# Wave_Fold_Osc_CTRL_V2.net
KiCad netlist of a schematic drawn in EAGLE
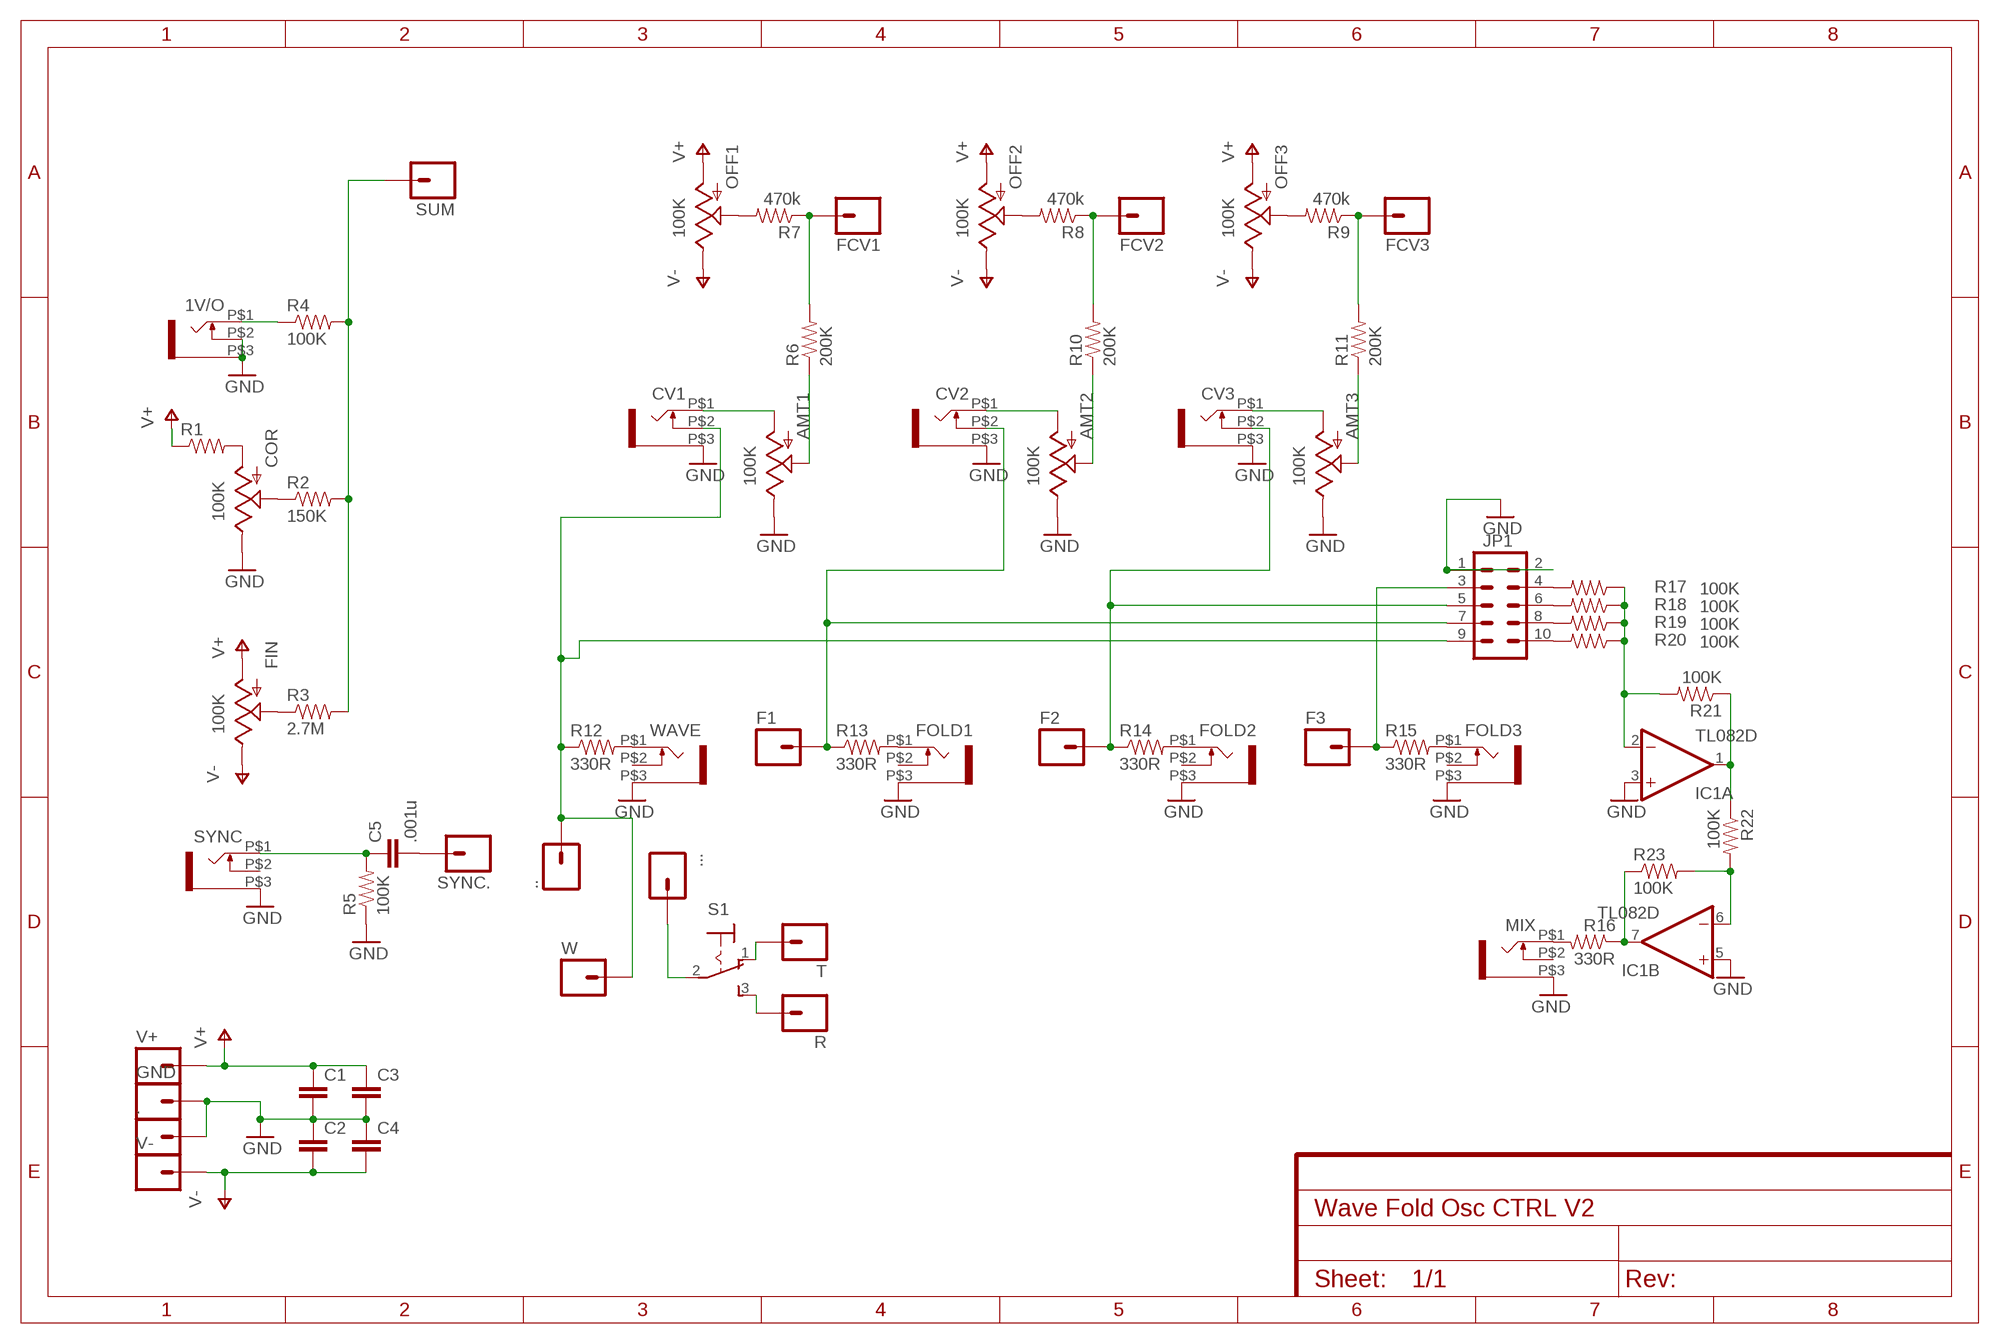
[diagram p0: schematic, sheet 1]

(export (version "E")
  (design (tool "Eeschema 10.0.6"))
  (components
    (comp (ref ".")
      (value "M01PTH")
      (footprint "eagle-import:1X01")
      (libsource (lib "eagle-import") (part "M01PTH"))
    )
    (comp (ref "..")
      (value "M01PTH")
      (footprint "eagle-import:1X01")
      (libsource (lib "eagle-import") (part "M01PTH"))
    )
    (comp (ref "...")
      (value "M01PTH")
      (footprint "eagle-import:1X01")
      (libsource (lib "eagle-import") (part "M01PTH"))
    )
    (comp (ref "1V/O")
      (value "WQP-PJ301M-12_JACK")
      (footprint "eagle-import:WQP-PJ301M-12_JACK")
      (libsource (lib "eagle-import") (part "WQP-PJ301M-12_JACK"))
    )
    (comp (ref "AMT1")
      (value "100K")
      (footprint "eagle-import:ALPS_POT")
      (libsource (lib "eagle-import") (part "POT"))
    )
    (comp (ref "AMT2")
      (value "100K")
      (footprint "eagle-import:ALPS_POT")
      (libsource (lib "eagle-import") (part "POT"))
    )
    (comp (ref "AMT3")
      (value "100K")
      (footprint "eagle-import:ALPS_POT")
      (libsource (lib "eagle-import") (part "POT"))
    )
    (comp (ref "C1")
      (value "CAP0805")
      (footprint "eagle-import:0805")
      (libsource (lib "eagle-import") (part "CAP0805"))
    )
    (comp (ref "C2")
      (value "CAP0805")
      (footprint "eagle-import:0805")
      (libsource (lib "eagle-import") (part "CAP0805"))
    )
    (comp (ref "C3")
      (value "CAP0805")
      (footprint "eagle-import:0805")
      (libsource (lib "eagle-import") (part "CAP0805"))
    )
    (comp (ref "C4")
      (value "CAP0805")
      (footprint "eagle-import:0805")
      (libsource (lib "eagle-import") (part "CAP0805"))
    )
    (comp (ref "C5")
      (value ".001u")
      (footprint "eagle-import:0805")
      (libsource (lib "eagle-import") (part "CAP0805"))
    )
    (comp (ref "COR")
      (value "100K")
      (footprint "eagle-import:ALPS_POT")
      (libsource (lib "eagle-import") (part "POT"))
    )
    (comp (ref "CV1")
      (value "WQP-PJ301M-12_JACK")
      (footprint "eagle-import:WQP-PJ301M-12_JACK")
      (libsource (lib "eagle-import") (part "WQP-PJ301M-12_JACK"))
    )
    (comp (ref "CV2")
      (value "WQP-PJ301M-12_JACK")
      (footprint "eagle-import:WQP-PJ301M-12_JACK")
      (libsource (lib "eagle-import") (part "WQP-PJ301M-12_JACK"))
    )
    (comp (ref "CV3")
      (value "WQP-PJ301M-12_JACK")
      (footprint "eagle-import:WQP-PJ301M-12_JACK")
      (libsource (lib "eagle-import") (part "WQP-PJ301M-12_JACK"))
    )
    (comp (ref "F1")
      (value "M01PTH")
      (footprint "eagle-import:1X01")
      (libsource (lib "eagle-import") (part "M01PTH"))
    )
    (comp (ref "F2")
      (value "M01PTH")
      (footprint "eagle-import:1X01")
      (libsource (lib "eagle-import") (part "M01PTH"))
    )
    (comp (ref "F3")
      (value "M01PTH")
      (footprint "eagle-import:1X01")
      (libsource (lib "eagle-import") (part "M01PTH"))
    )
    (comp (ref "FCV1")
      (value "M01PTH")
      (footprint "eagle-import:1X01")
      (libsource (lib "eagle-import") (part "M01PTH"))
    )
    (comp (ref "FCV2")
      (value "M01PTH")
      (footprint "eagle-import:1X01")
      (libsource (lib "eagle-import") (part "M01PTH"))
    )
    (comp (ref "FCV3")
      (value "M01PTH")
      (footprint "eagle-import:1X01")
      (libsource (lib "eagle-import") (part "M01PTH"))
    )
    (comp (ref "FIN")
      (value "100K")
      (footprint "eagle-import:ALPS_POT")
      (libsource (lib "eagle-import") (part "POT"))
    )
    (comp (ref "FOLD1")
      (value "WQP-PJ301M-12_JACK")
      (footprint "eagle-import:WQP-PJ301M-12_JACK")
      (libsource (lib "eagle-import") (part "WQP-PJ301M-12_JACK"))
    )
    (comp (ref "FOLD2")
      (value "WQP-PJ301M-12_JACK")
      (footprint "eagle-import:WQP-PJ301M-12_JACK")
      (libsource (lib "eagle-import") (part "WQP-PJ301M-12_JACK"))
    )
    (comp (ref "FOLD3")
      (value "WQP-PJ301M-12_JACK")
      (footprint "eagle-import:WQP-PJ301M-12_JACK")
      (libsource (lib "eagle-import") (part "WQP-PJ301M-12_JACK"))
    )
    (comp (ref "GND")
      (value "M01PTH")
      (footprint "eagle-import:1X01")
      (libsource (lib "eagle-import") (part "M01PTH"))
    )
    (comp (ref "IC1")
      (value "TL082D")
      (footprint "eagle-import:SO08")
      (libsource (lib "eagle-import") (part "TL082D"))
    )
    (comp (ref "JP1")
      (value "M05X2NO_SILK")
      (footprint "eagle-import:2X5_NOSILK")
      (libsource (lib "eagle-import") (part "M05X2NO_SILK"))
    )
    (comp (ref "MIX")
      (value "WQP-PJ301M-12_JACK")
      (footprint "eagle-import:WQP-PJ301M-12_JACK")
      (libsource (lib "eagle-import") (part "WQP-PJ301M-12_JACK"))
    )
    (comp (ref "OFF1")
      (value "100K")
      (footprint "eagle-import:ALPS_POT")
      (libsource (lib "eagle-import") (part "POT"))
    )
    (comp (ref "OFF2")
      (value "100K")
      (footprint "eagle-import:ALPS_POT")
      (libsource (lib "eagle-import") (part "POT"))
    )
    (comp (ref "OFF3")
      (value "100K")
      (footprint "eagle-import:ALPS_POT")
      (libsource (lib "eagle-import") (part "POT"))
    )
    (comp (ref "R")
      (value "M01PTH")
      (footprint "eagle-import:1X01")
      (libsource (lib "eagle-import") (part "M01PTH"))
    )
    (comp (ref "R1")
      (value "RESISTOR0805-RES")
      (footprint "eagle-import:0805")
      (libsource (lib "eagle-import") (part "RESISTOR0805-RES"))
    )
    (comp (ref "R2")
      (value "150K")
      (footprint "eagle-import:0805")
      (libsource (lib "eagle-import") (part "RESISTOR0805-RES"))
    )
    (comp (ref "R3")
      (value "2.7M")
      (footprint "eagle-import:0805")
      (libsource (lib "eagle-import") (part "RESISTOR0805-RES"))
    )
    (comp (ref "R4")
      (value "100K")
      (footprint "eagle-import:0805")
      (libsource (lib "eagle-import") (part "RESISTOR0805-RES"))
    )
    (comp (ref "R5")
      (value "100K")
      (footprint "eagle-import:0805")
      (libsource (lib "eagle-import") (part "RESISTOR0805-RES"))
    )
    (comp (ref "R6")
      (value "200K")
      (footprint "eagle-import:0805")
      (libsource (lib "eagle-import") (part "RESISTOR0805-RES"))
    )
    (comp (ref "R7")
      (value "470k")
      (footprint "eagle-import:0805")
      (libsource (lib "eagle-import") (part "RESISTOR0805-RES"))
    )
    (comp (ref "R8")
      (value "470k")
      (footprint "eagle-import:0805")
      (libsource (lib "eagle-import") (part "RESISTOR0805-RES"))
    )
    (comp (ref "R9")
      (value "470k")
      (footprint "eagle-import:0805")
      (libsource (lib "eagle-import") (part "RESISTOR0805-RES"))
    )
    (comp (ref "R10")
      (value "200K")
      (footprint "eagle-import:0805")
      (libsource (lib "eagle-import") (part "RESISTOR0805-RES"))
    )
    (comp (ref "R11")
      (value "200K")
      (footprint "eagle-import:0805")
      (libsource (lib "eagle-import") (part "RESISTOR0805-RES"))
    )
    (comp (ref "R12")
      (value "330R")
      (footprint "eagle-import:0805")
      (libsource (lib "eagle-import") (part "RESISTOR0805-RES"))
    )
    (comp (ref "R13")
      (value "330R")
      (footprint "eagle-import:0805")
      (libsource (lib "eagle-import") (part "RESISTOR0805-RES"))
    )
    (comp (ref "R14")
      (value "330R")
      (footprint "eagle-import:0805")
      (libsource (lib "eagle-import") (part "RESISTOR0805-RES"))
    )
    (comp (ref "R15")
      (value "330R")
      (footprint "eagle-import:0805")
      (libsource (lib "eagle-import") (part "RESISTOR0805-RES"))
    )
    (comp (ref "R16")
      (value "330R")
      (footprint "eagle-import:0805")
      (libsource (lib "eagle-import") (part "RESISTOR0805-RES"))
    )
    (comp (ref "R17")
      (value "100K")
      (footprint "eagle-import:0805")
      (libsource (lib "eagle-import") (part "RESISTOR0805-RES"))
    )
    (comp (ref "R18")
      (value "100K")
      (footprint "eagle-import:0805")
      (libsource (lib "eagle-import") (part "RESISTOR0805-RES"))
    )
    (comp (ref "R19")
      (value "100K")
      (footprint "eagle-import:0805")
      (libsource (lib "eagle-import") (part "RESISTOR0805-RES"))
    )
    (comp (ref "R20")
      (value "100K")
      (footprint "eagle-import:0805")
      (libsource (lib "eagle-import") (part "RESISTOR0805-RES"))
    )
    (comp (ref "R21")
      (value "100K")
      (footprint "eagle-import:0805")
      (libsource (lib "eagle-import") (part "RESISTOR0805-RES"))
    )
    (comp (ref "R22")
      (value "100K")
      (footprint "eagle-import:0805")
      (libsource (lib "eagle-import") (part "RESISTOR0805-RES"))
    )
    (comp (ref "R23")
      (value "100K")
      (footprint "eagle-import:0805")
      (libsource (lib "eagle-import") (part "RESISTOR0805-RES"))
    )
    (comp (ref "S1")
      (value "M9040P")
      (footprint "eagle-import:M9040P")
      (libsource (lib "eagle-import") (part "M9040P"))
    )
    (comp (ref "SUM")
      (value "M01PTH")
      (footprint "eagle-import:1X01")
      (libsource (lib "eagle-import") (part "M01PTH"))
    )
    (comp (ref "SYNC")
      (value "WQP-PJ301M-12_JACK")
      (footprint "eagle-import:WQP-PJ301M-12_JACK")
      (libsource (lib "eagle-import") (part "WQP-PJ301M-12_JACK"))
    )
    (comp (ref "SYNC.")
      (value "M01PTH")
      (footprint "eagle-import:1X01")
      (libsource (lib "eagle-import") (part "M01PTH"))
    )
    (comp (ref "T")
      (value "M01PTH")
      (footprint "eagle-import:1X01")
      (libsource (lib "eagle-import") (part "M01PTH"))
    )
    (comp (ref "V+")
      (value "M01PTH")
      (footprint "eagle-import:1X01")
      (libsource (lib "eagle-import") (part "M01PTH"))
    )
    (comp (ref "V-")
      (value "M01PTH")
      (footprint "eagle-import:1X01")
      (libsource (lib "eagle-import") (part "M01PTH"))
    )
    (comp (ref "W")
      (value "M01PTH")
      (footprint "eagle-import:1X01")
      (libsource (lib "eagle-import") (part "M01PTH"))
    )
    (comp (ref "WAVE")
      (value "WQP-PJ301M-12_JACK")
      (footprint "eagle-import:WQP-PJ301M-12_JACK")
      (libsource (lib "eagle-import") (part "WQP-PJ301M-12_JACK"))
    )
  )
  (nets
    (net (code "1") (name "GND") (class "Default")
      (node (ref ".") (pin "1") (pinfunction "1_1") (pintype "passive"))
      (node (ref "1V/O") (pin "P$2") (pinfunction "3_P$2") (pintype "passive"))
      (node (ref "1V/O") (pin "P$3") (pinfunction "1_P$3") (pintype "passive"))
      (node (ref "AMT1") (pin "P$1") (pinfunction "E_P$1") (pintype "passive"))
      (node (ref "AMT2") (pin "P$1") (pinfunction "E_P$1") (pintype "passive"))
      (node (ref "AMT3") (pin "P$1") (pinfunction "E_P$1") (pintype "passive"))
      (node (ref "C1") (pin "2") (pinfunction "2_2") (pintype "passive"))
      (node (ref "C2") (pin "1") (pinfunction "1_1") (pintype "passive"))
      (node (ref "C3") (pin "2") (pinfunction "2_2") (pintype "passive"))
      (node (ref "C4") (pin "1") (pinfunction "1_1") (pintype "passive"))
      (node (ref "COR") (pin "P$1") (pinfunction "E_P$1") (pintype "passive"))
      (node (ref "CV1") (pin "P$3") (pinfunction "1_P$3") (pintype "passive"))
      (node (ref "CV2") (pin "P$3") (pinfunction "1_P$3") (pintype "passive"))
      (node (ref "CV3") (pin "P$3") (pinfunction "1_P$3") (pintype "passive"))
      (node (ref "FOLD1") (pin "P$3") (pinfunction "1_P$3") (pintype "passive"))
      (node (ref "FOLD2") (pin "P$3") (pinfunction "1_P$3") (pintype "passive"))
      (node (ref "FOLD3") (pin "P$3") (pinfunction "1_P$3") (pintype "passive"))
      (node (ref "GND") (pin "1") (pinfunction "1_1") (pintype "passive"))
      (node (ref "IC1") (pin "3") (pinfunction "+IN_3") (pintype "input"))
      (node (ref "IC1") (pin "5") (pinfunction "+IN_5") (pintype "input"))
      (node (ref "JP1") (pin "1") (pinfunction "1_1") (pintype "passive"))
      (node (ref "JP1") (pin "2") (pinfunction "2_2") (pintype "passive"))
      (node (ref "MIX") (pin "P$3") (pinfunction "1_P$3") (pintype "passive"))
      (node (ref "R5") (pin "1") (pinfunction "1_1") (pintype "passive"))
      (node (ref "SYNC") (pin "P$3") (pinfunction "1_P$3") (pintype "passive"))
      (node (ref "WAVE") (pin "P$3") (pinfunction "1_P$3") (pintype "passive"))
    )
    (net (code "2") (name "Net-(1V/O-2)") (class "Default")
      (node (ref "1V/O") (pin "P$1") (pinfunction "2_P$1") (pintype "passive"))
      (node (ref "R4") (pin "1") (pinfunction "1_1") (pintype "passive"))
    )
    (net (code "3") (name "Net-(AMT1-A)") (class "Default")
      (node (ref "AMT1") (pin "P$3") (pinfunction "A_P$3") (pintype "passive"))
      (node (ref "CV1") (pin "P$1") (pinfunction "2_P$1") (pintype "passive"))
    )
    (net (code "4") (name "Net-(AMT1-S)") (class "Default")
      (node (ref "AMT1") (pin "P$2") (pinfunction "S_P$2") (pintype "passive"))
      (node (ref "R6") (pin "1") (pinfunction "1_1") (pintype "passive"))
    )
    (net (code "5") (name "Net-(AMT2-A)") (class "Default")
      (node (ref "AMT2") (pin "P$3") (pinfunction "A_P$3") (pintype "passive"))
      (node (ref "CV2") (pin "P$1") (pinfunction "2_P$1") (pintype "passive"))
    )
    (net (code "6") (name "Net-(AMT2-S)") (class "Default")
      (node (ref "AMT2") (pin "P$2") (pinfunction "S_P$2") (pintype "passive"))
      (node (ref "R10") (pin "1") (pinfunction "1_1") (pintype "passive"))
    )
    (net (code "7") (name "Net-(AMT3-A)") (class "Default")
      (node (ref "AMT3") (pin "P$3") (pinfunction "A_P$3") (pintype "passive"))
      (node (ref "CV3") (pin "P$1") (pinfunction "2_P$1") (pintype "passive"))
    )
    (net (code "8") (name "Net-(AMT3-S)") (class "Default")
      (node (ref "AMT3") (pin "P$2") (pinfunction "S_P$2") (pintype "passive"))
      (node (ref "R11") (pin "1") (pinfunction "1_1") (pintype "passive"))
    )
    (net (code "9") (name "Net-(C5-Pad2)") (class "Default")
      (node (ref "C5") (pin "2") (pinfunction "2_2") (pintype "passive"))
      (node (ref "SYNC.") (pin "1") (pinfunction "1_1") (pintype "passive"))
    )
    (net (code "10") (name "Net-(COR-A)") (class "Default")
      (node (ref "COR") (pin "P$3") (pinfunction "A_P$3") (pintype "passive"))
      (node (ref "R1") (pin "2") (pinfunction "2_2") (pintype "passive"))
    )
    (net (code "11") (name "Net-(COR-S)") (class "Default")
      (node (ref "COR") (pin "P$2") (pinfunction "S_P$2") (pintype "passive"))
      (node (ref "R2") (pin "1") (pinfunction "1_1") (pintype "passive"))
    )
    (net (code "12") (name "Net-(CV1-3)") (class "Default")
      (node (ref "..") (pin "1") (pinfunction "1_1") (pintype "passive"))
      (node (ref "CV1") (pin "P$2") (pinfunction "3_P$2") (pintype "passive"))
      (node (ref "JP1") (pin "9") (pinfunction "9_9") (pintype "passive"))
      (node (ref "R12") (pin "1") (pinfunction "1_1") (pintype "passive"))
      (node (ref "W") (pin "1") (pinfunction "1_1") (pintype "passive"))
    )
    (net (code "13") (name "Net-(CV2-3)") (class "Default")
      (node (ref "CV2") (pin "P$2") (pinfunction "3_P$2") (pintype "passive"))
      (node (ref "F1") (pin "1") (pinfunction "1_1") (pintype "passive"))
      (node (ref "JP1") (pin "7") (pinfunction "7_7") (pintype "passive"))
      (node (ref "R13") (pin "1") (pinfunction "1_1") (pintype "passive"))
    )
    (net (code "14") (name "Net-(CV3-3)") (class "Default")
      (node (ref "CV3") (pin "P$2") (pinfunction "3_P$2") (pintype "passive"))
      (node (ref "F2") (pin "1") (pinfunction "1_1") (pintype "passive"))
      (node (ref "JP1") (pin "5") (pinfunction "5_5") (pintype "passive"))
      (node (ref "R14") (pin "1") (pinfunction "1_1") (pintype "passive"))
    )
    (net (code "15") (name "Net-(F3-Pad1)") (class "Default")
      (node (ref "F3") (pin "1") (pinfunction "1_1") (pintype "passive"))
      (node (ref "JP1") (pin "3") (pinfunction "3_3") (pintype "passive"))
      (node (ref "R15") (pin "1") (pinfunction "1_1") (pintype "passive"))
    )
    (net (code "16") (name "Net-(FCV1-Pad1)") (class "Default")
      (node (ref "FCV1") (pin "1") (pinfunction "1_1") (pintype "passive"))
      (node (ref "R6") (pin "2") (pinfunction "2_2") (pintype "passive"))
      (node (ref "R7") (pin "1") (pinfunction "1_1") (pintype "passive"))
    )
    (net (code "17") (name "Net-(FCV2-Pad1)") (class "Default")
      (node (ref "FCV2") (pin "1") (pinfunction "1_1") (pintype "passive"))
      (node (ref "R10") (pin "2") (pinfunction "2_2") (pintype "passive"))
      (node (ref "R8") (pin "1") (pinfunction "1_1") (pintype "passive"))
    )
    (net (code "18") (name "Net-(FCV3-Pad1)") (class "Default")
      (node (ref "FCV3") (pin "1") (pinfunction "1_1") (pintype "passive"))
      (node (ref "R11") (pin "2") (pinfunction "2_2") (pintype "passive"))
      (node (ref "R9") (pin "1") (pinfunction "1_1") (pintype "passive"))
    )
    (net (code "19") (name "Net-(FIN-S)") (class "Default")
      (node (ref "FIN") (pin "P$2") (pinfunction "S_P$2") (pintype "passive"))
      (node (ref "R3") (pin "1") (pinfunction "1_1") (pintype "passive"))
    )
    (net (code "20") (name "Net-(FOLD1-2)") (class "Default")
      (node (ref "FOLD1") (pin "P$1") (pinfunction "2_P$1") (pintype "passive"))
      (node (ref "R13") (pin "2") (pinfunction "2_2") (pintype "passive"))
    )
    (net (code "21") (name "Net-(FOLD2-2)") (class "Default")
      (node (ref "FOLD2") (pin "P$1") (pinfunction "2_P$1") (pintype "passive"))
      (node (ref "R14") (pin "2") (pinfunction "2_2") (pintype "passive"))
    )
    (net (code "22") (name "Net-(FOLD3-2)") (class "Default")
      (node (ref "FOLD3") (pin "P$1") (pinfunction "2_P$1") (pintype "passive"))
      (node (ref "R15") (pin "2") (pinfunction "2_2") (pintype "passive"))
    )
    (net (code "23") (name "Net-(IC1A--IN)") (class "Default")
      (node (ref "IC1") (pin "2") (pinfunction "-IN_2") (pintype "input"))
      (node (ref "R17") (pin "1") (pinfunction "1_1") (pintype "passive"))
      (node (ref "R18") (pin "1") (pinfunction "1_1") (pintype "passive"))
      (node (ref "R19") (pin "1") (pinfunction "1_1") (pintype "passive"))
      (node (ref "R20") (pin "1") (pinfunction "1_1") (pintype "passive"))
      (node (ref "R21") (pin "2") (pinfunction "2_2") (pintype "passive"))
    )
    (net (code "24") (name "Net-(IC1A-OUT)") (class "Default")
      (node (ref "IC1") (pin "1") (pinfunction "OUT_1") (pintype "output"))
      (node (ref "R21") (pin "1") (pinfunction "1_1") (pintype "passive"))
      (node (ref "R22") (pin "1") (pinfunction "1_1") (pintype "passive"))
    )
    (net (code "25") (name "Net-(IC1B--IN)") (class "Default")
      (node (ref "IC1") (pin "6") (pinfunction "-IN_6") (pintype "input"))
      (node (ref "R22") (pin "2") (pinfunction "2_2") (pintype "passive"))
      (node (ref "R23") (pin "2") (pinfunction "2_2") (pintype "passive"))
    )
    (net (code "26") (name "Net-(IC1B-OUT)") (class "Default")
      (node (ref "IC1") (pin "7") (pinfunction "OUT_7") (pintype "output"))
      (node (ref "R16") (pin "1") (pinfunction "1_1") (pintype "passive"))
      (node (ref "R23") (pin "1") (pinfunction "1_1") (pintype "passive"))
    )
    (net (code "27") (name "Net-(JP1-Pad4)") (class "Default")
      (node (ref "JP1") (pin "4") (pinfunction "4_4") (pintype "passive"))
      (node (ref "R17") (pin "2") (pinfunction "2_2") (pintype "passive"))
    )
    (net (code "28") (name "Net-(JP1-Pad6)") (class "Default")
      (node (ref "JP1") (pin "6") (pinfunction "6_6") (pintype "passive"))
      (node (ref "R18") (pin "2") (pinfunction "2_2") (pintype "passive"))
    )
    (net (code "29") (name "Net-(JP1-Pad8)") (class "Default")
      (node (ref "JP1") (pin "8") (pinfunction "8_8") (pintype "passive"))
      (node (ref "R19") (pin "2") (pinfunction "2_2") (pintype "passive"))
    )
    (net (code "30") (name "Net-(JP1-Pad10)") (class "Default")
      (node (ref "JP1") (pin "10") (pinfunction "10_10") (pintype "passive"))
      (node (ref "R20") (pin "2") (pinfunction "2_2") (pintype "passive"))
    )
    (net (code "31") (name "Net-(MIX-2)") (class "Default")
      (node (ref "MIX") (pin "P$1") (pinfunction "2_P$1") (pintype "passive"))
      (node (ref "R16") (pin "2") (pinfunction "2_2") (pintype "passive"))
    )
    (net (code "32") (name "Net-(OFF1-S)") (class "Default")
      (node (ref "OFF1") (pin "P$2") (pinfunction "S_P$2") (pintype "passive"))
      (node (ref "R7") (pin "2") (pinfunction "2_2") (pintype "passive"))
    )
    (net (code "33") (name "Net-(OFF2-S)") (class "Default")
      (node (ref "OFF2") (pin "P$2") (pinfunction "S_P$2") (pintype "passive"))
      (node (ref "R8") (pin "2") (pinfunction "2_2") (pintype "passive"))
    )
    (net (code "34") (name "Net-(OFF3-S)") (class "Default")
      (node (ref "OFF3") (pin "P$2") (pinfunction "S_P$2") (pintype "passive"))
      (node (ref "R9") (pin "2") (pinfunction "2_2") (pintype "passive"))
    )
    (net (code "35") (name "Net-(R2-Pad2)") (class "Default")
      (node (ref "R2") (pin "2") (pinfunction "2_2") (pintype "passive"))
      (node (ref "R3") (pin "2") (pinfunction "2_2") (pintype "passive"))
      (node (ref "R4") (pin "2") (pinfunction "2_2") (pintype "passive"))
      (node (ref "SUM") (pin "1") (pinfunction "1_1") (pintype "passive"))
    )
    (net (code "36") (name "Net-(S1-O)") (class "Default")
      (node (ref "S1") (pin "1") (pinfunction "O_1") (pintype "passive"))
      (node (ref "T") (pin "1") (pinfunction "1_1") (pintype "passive"))
    )
    (net (code "37") (name "Net-(S1-P)") (class "Default")
      (node (ref "...") (pin "1") (pinfunction "1_1") (pintype "passive"))
      (node (ref "S1") (pin "2") (pinfunction "P_2") (pintype "passive"))
    )
    (net (code "38") (name "Net-(S1-S)") (class "Default")
      (node (ref "R") (pin "1") (pinfunction "1_1") (pintype "passive"))
      (node (ref "S1") (pin "3") (pinfunction "S_3") (pintype "passive"))
    )
    (net (code "39") (name "Net-(SYNC-2)") (class "Default")
      (node (ref "C5") (pin "1") (pinfunction "1_1") (pintype "passive"))
      (node (ref "R5") (pin "2") (pinfunction "2_2") (pintype "passive"))
      (node (ref "SYNC") (pin "P$1") (pinfunction "2_P$1") (pintype "passive"))
    )
    (net (code "40") (name "Net-(WAVE-2)") (class "Default")
      (node (ref "R12") (pin "2") (pinfunction "2_2") (pintype "passive"))
      (node (ref "WAVE") (pin "P$1") (pinfunction "2_P$1") (pintype "passive"))
    )
    (net (code "41") (name "V+") (class "Default")
      (node (ref "C1") (pin "1") (pinfunction "1_1") (pintype "passive"))
      (node (ref "C3") (pin "1") (pinfunction "1_1") (pintype "passive"))
      (node (ref "FIN") (pin "P$3") (pinfunction "A_P$3") (pintype "passive"))
      (node (ref "OFF1") (pin "P$3") (pinfunction "A_P$3") (pintype "passive"))
      (node (ref "OFF2") (pin "P$3") (pinfunction "A_P$3") (pintype "passive"))
      (node (ref "OFF3") (pin "P$3") (pinfunction "A_P$3") (pintype "passive"))
      (node (ref "R1") (pin "1") (pinfunction "1_1") (pintype "passive"))
      (node (ref "V+") (pin "1") (pinfunction "1_1") (pintype "passive"))
    )
    (net (code "42") (name "V-") (class "Default")
      (node (ref "C2") (pin "2") (pinfunction "2_2") (pintype "passive"))
      (node (ref "C4") (pin "2") (pinfunction "2_2") (pintype "passive"))
      (node (ref "FIN") (pin "P$1") (pinfunction "E_P$1") (pintype "passive"))
      (node (ref "OFF1") (pin "P$1") (pinfunction "E_P$1") (pintype "passive"))
      (node (ref "OFF2") (pin "P$1") (pinfunction "E_P$1") (pintype "passive"))
      (node (ref "OFF3") (pin "P$1") (pinfunction "E_P$1") (pintype "passive"))
      (node (ref "V-") (pin "1") (pinfunction "1_1") (pintype "passive"))
    )
    (net (code "43") (name "unconnected-(FOLD1-3-PadP$2)") (class "Default")
      (node (ref "FOLD1") (pin "P$2") (pinfunction "3_P$2") (pintype "passive"))
    )
    (net (code "44") (name "unconnected-(FOLD2-3-PadP$2)") (class "Default")
      (node (ref "FOLD2") (pin "P$2") (pinfunction "3_P$2") (pintype "passive"))
    )
    (net (code "45") (name "unconnected-(FOLD3-3-PadP$2)") (class "Default")
      (node (ref "FOLD3") (pin "P$2") (pinfunction "3_P$2") (pintype "passive"))
    )
    (net (code "46") (name "unconnected-(MIX-3-PadP$2)") (class "Default")
      (node (ref "MIX") (pin "P$2") (pinfunction "3_P$2") (pintype "passive"))
    )
    (net (code "47") (name "unconnected-(SYNC-3-PadP$2)") (class "Default")
      (node (ref "SYNC") (pin "P$2") (pinfunction "3_P$2") (pintype "passive"))
    )
    (net (code "48") (name "unconnected-(WAVE-3-PadP$2)") (class "Default")
      (node (ref "WAVE") (pin "P$2") (pinfunction "3_P$2") (pintype "passive"))
    )
  )
)
